# untitled.net
KiCad netlist of a schematic drawn in EAGLE
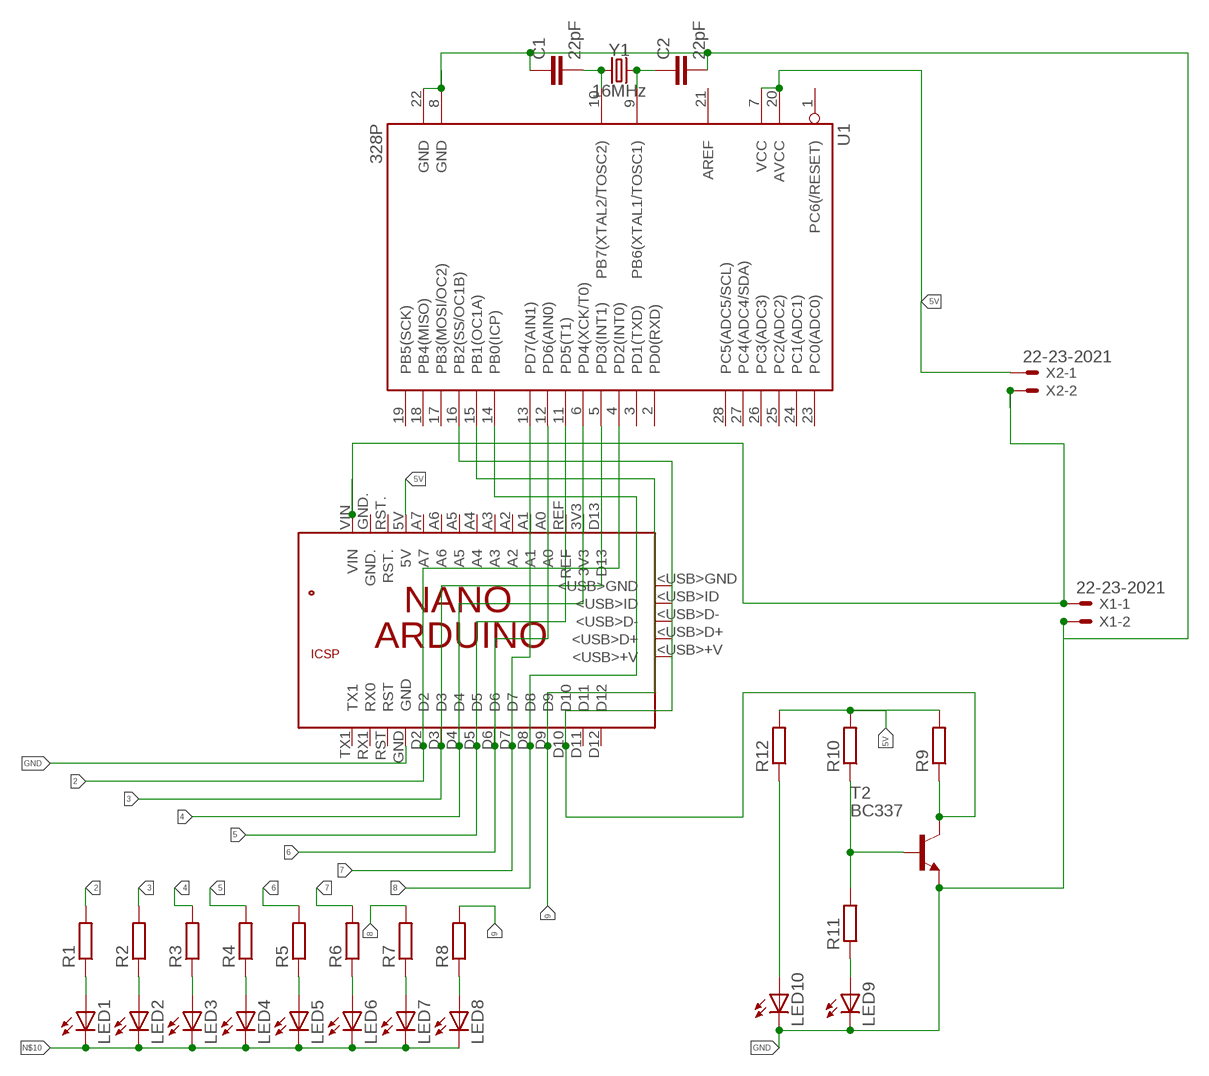
[diagram p0: schematic, sheet 1]

(export (version "E")
  (design (tool "Eeschema 10.0.6"))
  (components
    (comp (ref "C1")
      (value "22pF")
      (footprint "eagle-import:CAP-PTH-2.54")
      (libsource (lib "eagle-import") (part "22PF-PTH-2.54MM-200V-5%"))
    )
    (comp (ref "C2")
      (value "22pF")
      (footprint "eagle-import:CAP-PTH-2.54")
      (libsource (lib "eagle-import") (part "22PF-PTH-2.54MM-200V-5%"))
    )
    (comp (ref "LED1")
      (value "LED5MM")
      (footprint "eagle-import:LED5MM")
      (libsource (lib "eagle-import") (part "LED5MM"))
    )
    (comp (ref "LED2")
      (value "LED5MM")
      (footprint "eagle-import:LED5MM")
      (libsource (lib "eagle-import") (part "LED5MM"))
    )
    (comp (ref "LED3")
      (value "LED5MM")
      (footprint "eagle-import:LED5MM")
      (libsource (lib "eagle-import") (part "LED5MM"))
    )
    (comp (ref "LED4")
      (value "LED5MM")
      (footprint "eagle-import:LED5MM")
      (libsource (lib "eagle-import") (part "LED5MM"))
    )
    (comp (ref "LED5")
      (value "LED5MM")
      (footprint "eagle-import:LED5MM")
      (libsource (lib "eagle-import") (part "LED5MM"))
    )
    (comp (ref "LED6")
      (value "LED5MM")
      (footprint "eagle-import:LED5MM")
      (libsource (lib "eagle-import") (part "LED5MM"))
    )
    (comp (ref "LED7")
      (value "LED5MM")
      (footprint "eagle-import:LED5MM")
      (libsource (lib "eagle-import") (part "LED5MM"))
    )
    (comp (ref "LED8")
      (value "LED5MM")
      (footprint "eagle-import:LED5MM")
      (libsource (lib "eagle-import") (part "LED5MM"))
    )
    (comp (ref "LED9")
      (value "LED5MM")
      (footprint "eagle-import:LED5MM")
      (libsource (lib "eagle-import") (part "LED5MM"))
    )
    (comp (ref "LED10")
      (value "LED5MM")
      (footprint "eagle-import:LED5MM")
      (libsource (lib "eagle-import") (part "LED5MM"))
    )
    (comp (ref "PCB1")
      (value "ARDUINO_NANO")
      (footprint "eagle-import:ARDUINO_NANO")
      (libsource (lib "eagle-import") (part "ARDUINO_NANO"))
    )
    (comp (ref "R1")
      (value "R-EU_0207/10")
      (footprint "eagle-import:0207_10")
      (libsource (lib "eagle-import") (part "R-EU_0207/10"))
    )
    (comp (ref "R2")
      (value "R-EU_0207/10")
      (footprint "eagle-import:0207_10")
      (libsource (lib "eagle-import") (part "R-EU_0207/10"))
    )
    (comp (ref "R3")
      (value "R-EU_0207/10")
      (footprint "eagle-import:0207_10")
      (libsource (lib "eagle-import") (part "R-EU_0207/10"))
    )
    (comp (ref "R4")
      (value "R-EU_0207/10")
      (footprint "eagle-import:0207_10")
      (libsource (lib "eagle-import") (part "R-EU_0207/10"))
    )
    (comp (ref "R5")
      (value "R-EU_0207/10")
      (footprint "eagle-import:0207_10")
      (libsource (lib "eagle-import") (part "R-EU_0207/10"))
    )
    (comp (ref "R6")
      (value "R-EU_0207/10")
      (footprint "eagle-import:0207_10")
      (libsource (lib "eagle-import") (part "R-EU_0207/10"))
    )
    (comp (ref "R7")
      (value "R-EU_0207/10")
      (footprint "eagle-import:0207_10")
      (libsource (lib "eagle-import") (part "R-EU_0207/10"))
    )
    (comp (ref "R8")
      (value "R-EU_0207/10")
      (footprint "eagle-import:0207_10")
      (libsource (lib "eagle-import") (part "R-EU_0207/10"))
    )
    (comp (ref "R9")
      (value "R-EU_0207/10")
      (footprint "eagle-import:0207_10")
      (libsource (lib "eagle-import") (part "R-EU_0207/10"))
    )
    (comp (ref "R10")
      (value "R-EU_0207/10")
      (footprint "eagle-import:0207_10")
      (libsource (lib "eagle-import") (part "R-EU_0207/10"))
    )
    (comp (ref "R11")
      (value "R-EU_0207/10")
      (footprint "eagle-import:0207_10")
      (libsource (lib "eagle-import") (part "R-EU_0207/10"))
    )
    (comp (ref "R12")
      (value "R-EU_0207/10")
      (footprint "eagle-import:0207_10")
      (libsource (lib "eagle-import") (part "R-EU_0207/10"))
    )
    (comp (ref "T2")
      (value "BC337")
      (footprint "eagle-import:TO92")
      (libsource (lib "eagle-import") (part "BC337"))
    )
    (comp (ref "U1")
      (value "328P")
      (footprint "eagle-import:DIP28")
      (libsource (lib "eagle-import") (part "ATMEGA328P_PDIP"))
    )
    (comp (ref "X1")
      (value "22-23-2021")
      (footprint "eagle-import:22-23-2021")
      (fields (field (name "MF") "MOLEX"))
      (libsource (lib "eagle-import") (part "22-23-2021"))
    )
    (comp (ref "X2")
      (value "22-23-2021")
      (footprint "eagle-import:22-23-2021")
      (fields (field (name "MF") "MOLEX"))
      (libsource (lib "eagle-import") (part "con-molex_165_22-23-2021"))
    )
    (comp (ref "Y1")
      (value "16MHz")
      (footprint "eagle-import:HC49US")
      (libsource (lib "eagle-import") (part "CRYSTAL-16MHZPTH-HC49US"))
    )
  )
  (nets
    (net (code "1") (name "2") (class "Default")
      (node (ref "PCB1") (pin "D2") (pinfunction "D2_D2") (pintype "bidirectional"))
      (node (ref "R1") (pin "2") (pinfunction "2_2") (pintype "passive"))
      (node (ref "U1") (pin "4") (pinfunction "PD2(INT0)_4") (pintype "bidirectional"))
    )
    (net (code "2") (name "3") (class "Default")
      (node (ref "PCB1") (pin "D3") (pinfunction "D3_D3") (pintype "bidirectional"))
      (node (ref "R2") (pin "2") (pinfunction "2_2") (pintype "passive"))
      (node (ref "U1") (pin "5") (pinfunction "PD3(INT1)_5") (pintype "bidirectional"))
    )
    (net (code "3") (name "4") (class "Default")
      (node (ref "PCB1") (pin "D4") (pinfunction "D4_D4") (pintype "bidirectional"))
      (node (ref "R3") (pin "2") (pinfunction "2_2") (pintype "passive"))
      (node (ref "U1") (pin "6") (pinfunction "PD4(XCK/T0)_6") (pintype "bidirectional"))
    )
    (net (code "4") (name "5") (class "Default")
      (node (ref "PCB1") (pin "D5") (pinfunction "D5_D5") (pintype "bidirectional"))
      (node (ref "R4") (pin "2") (pinfunction "2_2") (pintype "passive"))
      (node (ref "U1") (pin "11") (pinfunction "PD5(T1)_11") (pintype "bidirectional"))
    )
    (net (code "5") (name "5V") (class "Default")
      (node (ref "PCB1") (pin "5V") (pinfunction "5V_5V") (pintype "bidirectional"))
      (node (ref "R10") (pin "2") (pinfunction "2_2") (pintype "passive"))
      (node (ref "R12") (pin "2") (pinfunction "2_2") (pintype "passive"))
      (node (ref "R9") (pin "2") (pinfunction "2_2") (pintype "passive"))
      (node (ref "U1") (pin "20") (pinfunction "AVCC_20") (pintype "bidirectional"))
      (node (ref "U1") (pin "7") (pinfunction "VCC_7") (pintype "bidirectional"))
      (node (ref "X2") (pin "1") (pinfunction "S_1") (pintype "passive"))
    )
    (net (code "6") (name "6") (class "Default")
      (node (ref "PCB1") (pin "D6") (pinfunction "D6_D6") (pintype "bidirectional"))
      (node (ref "R5") (pin "2") (pinfunction "2_2") (pintype "passive"))
      (node (ref "U1") (pin "12") (pinfunction "PD6(AIN0)_12") (pintype "bidirectional"))
    )
    (net (code "7") (name "7") (class "Default")
      (node (ref "PCB1") (pin "D7") (pinfunction "D7_D7") (pintype "bidirectional"))
      (node (ref "R6") (pin "2") (pinfunction "2_2") (pintype "passive"))
      (node (ref "U1") (pin "13") (pinfunction "PD7(AIN1)_13") (pintype "bidirectional"))
    )
    (net (code "8") (name "8") (class "Default")
      (node (ref "PCB1") (pin "D8") (pinfunction "D8_D8") (pintype "bidirectional"))
      (node (ref "R7") (pin "2") (pinfunction "2_2") (pintype "passive"))
      (node (ref "U1") (pin "14") (pinfunction "PB0(ICP)_14") (pintype "bidirectional"))
    )
    (net (code "9") (name "9") (class "Default")
      (node (ref "PCB1") (pin "D9") (pinfunction "D9_D9") (pintype "bidirectional"))
      (node (ref "R8") (pin "2") (pinfunction "2_2") (pintype "passive"))
      (node (ref "U1") (pin "15") (pinfunction "PB1(OC1A)_15") (pintype "bidirectional"))
    )
    (net (code "10") (name "GND") (class "Default")
      (node (ref "C1") (pin "1") (pinfunction "1_1") (pintype "passive"))
      (node (ref "C2") (pin "2") (pinfunction "2_2") (pintype "passive"))
      (node (ref "LED10") (pin "K") (pinfunction "C_K") (pintype "passive"))
      (node (ref "LED9") (pin "K") (pinfunction "C_K") (pintype "passive"))
      (node (ref "PCB1") (pin "GND") (pinfunction "GND_GND") (pintype "bidirectional"))
      (node (ref "T2") (pin "1") (pinfunction "E_1") (pintype "passive"))
      (node (ref "U1") (pin "22") (pinfunction "GND_22") (pintype "bidirectional"))
      (node (ref "U1") (pin "8") (pinfunction "GND_8") (pintype "bidirectional"))
      (node (ref "X1") (pin "2") (pinfunction "S_2") (pintype "passive"))
    )
    (net (code "11") (name "N$10") (class "Default")
      (node (ref "LED1") (pin "K") (pinfunction "C_K") (pintype "passive"))
      (node (ref "LED2") (pin "K") (pinfunction "C_K") (pintype "passive"))
      (node (ref "LED3") (pin "K") (pinfunction "C_K") (pintype "passive"))
      (node (ref "LED4") (pin "K") (pinfunction "C_K") (pintype "passive"))
      (node (ref "LED5") (pin "K") (pinfunction "C_K") (pintype "passive"))
      (node (ref "LED6") (pin "K") (pinfunction "C_K") (pintype "passive"))
      (node (ref "LED7") (pin "K") (pinfunction "C_K") (pintype "passive"))
      (node (ref "LED8") (pin "K") (pinfunction "C_K") (pintype "passive"))
    )
    (net (code "12") (name "Net-(LED1-PadA)") (class "Default")
      (node (ref "LED1") (pin "A") (pinfunction "A_A") (pintype "passive"))
      (node (ref "R1") (pin "1") (pinfunction "1_1") (pintype "passive"))
    )
    (net (code "13") (name "Net-(LED2-PadA)") (class "Default")
      (node (ref "LED2") (pin "A") (pinfunction "A_A") (pintype "passive"))
      (node (ref "R2") (pin "1") (pinfunction "1_1") (pintype "passive"))
    )
    (net (code "14") (name "Net-(LED3-PadA)") (class "Default")
      (node (ref "LED3") (pin "A") (pinfunction "A_A") (pintype "passive"))
      (node (ref "R3") (pin "1") (pinfunction "1_1") (pintype "passive"))
    )
    (net (code "15") (name "Net-(LED4-PadA)") (class "Default")
      (node (ref "LED4") (pin "A") (pinfunction "A_A") (pintype "passive"))
      (node (ref "R4") (pin "1") (pinfunction "1_1") (pintype "passive"))
    )
    (net (code "16") (name "Net-(LED5-PadA)") (class "Default")
      (node (ref "LED5") (pin "A") (pinfunction "A_A") (pintype "passive"))
      (node (ref "R5") (pin "1") (pinfunction "1_1") (pintype "passive"))
    )
    (net (code "17") (name "Net-(LED6-PadA)") (class "Default")
      (node (ref "LED6") (pin "A") (pinfunction "A_A") (pintype "passive"))
      (node (ref "R6") (pin "1") (pinfunction "1_1") (pintype "passive"))
    )
    (net (code "18") (name "Net-(LED7-PadA)") (class "Default")
      (node (ref "LED7") (pin "A") (pinfunction "A_A") (pintype "passive"))
      (node (ref "R7") (pin "1") (pinfunction "1_1") (pintype "passive"))
    )
    (net (code "19") (name "Net-(LED8-PadA)") (class "Default")
      (node (ref "LED8") (pin "A") (pinfunction "A_A") (pintype "passive"))
      (node (ref "R8") (pin "1") (pinfunction "1_1") (pintype "passive"))
    )
    (net (code "20") (name "Net-(LED9-PadA)") (class "Default")
      (node (ref "LED9") (pin "A") (pinfunction "A_A") (pintype "passive"))
      (node (ref "R11") (pin "1") (pinfunction "1_1") (pintype "passive"))
    )
    (net (code "21") (name "Net-(LED10-PadA)") (class "Default")
      (node (ref "LED10") (pin "A") (pinfunction "A_A") (pintype "passive"))
      (node (ref "R12") (pin "1") (pinfunction "1_1") (pintype "passive"))
    )
    (net (code "22") (name "Net-(T2-B)") (class "Default")
      (node (ref "R10") (pin "1") (pinfunction "1_1") (pintype "passive"))
      (node (ref "R11") (pin "2") (pinfunction "2_2") (pintype "passive"))
      (node (ref "T2") (pin "2") (pinfunction "B_2") (pintype "passive"))
    )
    (net (code "23") (name "Net-(T2-C)") (class "Default")
      (node (ref "PCB1") (pin "D10") (pinfunction "D10_D10") (pintype "bidirectional"))
      (node (ref "R9") (pin "1") (pinfunction "1_1") (pintype "passive"))
      (node (ref "T2") (pin "3") (pinfunction "C_3") (pintype "passive"))
      (node (ref "U1") (pin "16") (pinfunction "PB2(SS/OC1B)_16") (pintype "bidirectional"))
    )
    (net (code "24") (name "Net-(U1-PB6(XTAL1{slash}TOSC1))") (class "Default")
      (node (ref "C2") (pin "1") (pinfunction "1_1") (pintype "passive"))
      (node (ref "U1") (pin "9") (pinfunction "PB6(XTAL1/TOSC1)_9") (pintype "bidirectional"))
      (node (ref "Y1") (pin "2") (pinfunction "2_2") (pintype "passive"))
    )
    (net (code "25") (name "Net-(U1-PB7(XTAL2{slash}TOSC2))") (class "Default")
      (node (ref "C1") (pin "2") (pinfunction "2_2") (pintype "passive"))
      (node (ref "U1") (pin "10") (pinfunction "PB7(XTAL2/TOSC2)_10") (pintype "bidirectional"))
      (node (ref "Y1") (pin "1") (pinfunction "1_1") (pintype "passive"))
    )
    (net (code "26") (name "Net-(X1A-S)") (class "Default")
      (node (ref "PCB1") (pin "VIN") (pinfunction "VIN_VIN") (pintype "bidirectional"))
      (node (ref "X1") (pin "1") (pinfunction "S_1") (pintype "passive"))
      (node (ref "X2") (pin "2") (pinfunction "S_2") (pintype "passive"))
    )
    (net (code "27") (name "unconnected-(PCB1-Pad3V3)") (class "Default")
      (node (ref "PCB1") (pin "3V3") (pinfunction "3V3_3V3") (pintype "bidirectional"))
    )
    (net (code "28") (name "unconnected-(PCB1-Pad5V.)") (class "Default")
      (node (ref "PCB1") (pin "5V.") (pinfunction "5V._5V.") (pintype "bidirectional"))
    )
    (net (code "29") (name "unconnected-(PCB1-Pad<USB>+V)") (class "Default")
      (node (ref "PCB1") (pin "<USB>+V") (pinfunction "<USB>+V_<USB>+V") (pintype "bidirectional"))
    )
    (net (code "30") (name "unconnected-(PCB1-Pad<USB>D+)") (class "Default")
      (node (ref "PCB1") (pin "<USB>D+") (pinfunction "<USB>D+_<USB>D+") (pintype "bidirectional"))
    )
    (net (code "31") (name "unconnected-(PCB1-Pad<USB>D-)") (class "Default")
      (node (ref "PCB1") (pin "<USB>D-") (pinfunction "<USB>D-_<USB>D-") (pintype "bidirectional"))
    )
    (net (code "32") (name "unconnected-(PCB1-Pad<USB>GND)") (class "Default")
      (node (ref "PCB1") (pin "<USB>GND") (pinfunction "<USB>GND_<USB>GND") (pintype "bidirectional"))
    )
    (net (code "33") (name "unconnected-(PCB1-Pad<USB>ID)") (class "Default")
      (node (ref "PCB1") (pin "<USB>ID") (pinfunction "<USB>ID_<USB>ID") (pintype "bidirectional"))
    )
    (net (code "34") (name "unconnected-(PCB1-PadA0)") (class "Default")
      (node (ref "PCB1") (pin "A0") (pinfunction "A0_A0") (pintype "bidirectional"))
    )
    (net (code "35") (name "unconnected-(PCB1-PadA1)") (class "Default")
      (node (ref "PCB1") (pin "A1") (pinfunction "A1_A1") (pintype "bidirectional"))
    )
    (net (code "36") (name "unconnected-(PCB1-PadA2)") (class "Default")
      (node (ref "PCB1") (pin "A2") (pinfunction "A2_A2") (pintype "bidirectional"))
    )
    (net (code "37") (name "unconnected-(PCB1-PadA3)") (class "Default")
      (node (ref "PCB1") (pin "A3") (pinfunction "A3_A3") (pintype "bidirectional"))
    )
    (net (code "38") (name "unconnected-(PCB1-PadA4)") (class "Default")
      (node (ref "PCB1") (pin "A4") (pinfunction "A4_A4") (pintype "bidirectional"))
    )
    (net (code "39") (name "unconnected-(PCB1-PadA5)") (class "Default")
      (node (ref "PCB1") (pin "A5") (pinfunction "A5_A5") (pintype "bidirectional"))
    )
    (net (code "40") (name "unconnected-(PCB1-PadA6)") (class "Default")
      (node (ref "PCB1") (pin "A6") (pinfunction "A6_A6") (pintype "bidirectional"))
    )
    (net (code "41") (name "unconnected-(PCB1-PadA7)") (class "Default")
      (node (ref "PCB1") (pin "A7") (pinfunction "A7_A7") (pintype "bidirectional"))
    )
    (net (code "42") (name "unconnected-(PCB1-PadD11)") (class "Default")
      (node (ref "PCB1") (pin "D11") (pinfunction "D11_D11") (pintype "bidirectional"))
    )
    (net (code "43") (name "unconnected-(PCB1-PadD12)") (class "Default")
      (node (ref "PCB1") (pin "D12") (pinfunction "D12_D12") (pintype "bidirectional"))
    )
    (net (code "44") (name "unconnected-(PCB1-PadD13)") (class "Default")
      (node (ref "PCB1") (pin "D13") (pinfunction "D13_D13") (pintype "bidirectional"))
    )
    (net (code "45") (name "unconnected-(PCB1-PadGND.)") (class "Default")
      (node (ref "PCB1") (pin "GND.") (pinfunction "GND._GND.") (pintype "bidirectional"))
    )
    (net (code "46") (name "unconnected-(PCB1-PadGND_)") (class "Default")
      (node (ref "PCB1") (pin "GND_") (pinfunction "GND__GND_") (pintype "bidirectional"))
    )
    (net (code "47") (name "unconnected-(PCB1-PadMISO)") (class "Default")
      (node (ref "PCB1") (pin "MISO") (pinfunction "MISO_MISO") (pintype "bidirectional"))
    )
    (net (code "48") (name "unconnected-(PCB1-PadMOSI)") (class "Default")
      (node (ref "PCB1") (pin "MOSI") (pinfunction "MOSI_MOSI") (pintype "bidirectional"))
    )
    (net (code "49") (name "unconnected-(PCB1-PadREF)") (class "Default")
      (node (ref "PCB1") (pin "REF") (pinfunction "REF_REF") (pintype "bidirectional"))
    )
    (net (code "50") (name "unconnected-(PCB1-PadRESET..)") (class "Default")
      (node (ref "PCB1") (pin "RESET..") (pinfunction "RESET.._RESET..") (pintype "bidirectional"))
    )
    (net (code "51") (name "unconnected-(PCB1-PadRST)") (class "Default")
      (node (ref "PCB1") (pin "RST") (pinfunction "RST_RST") (pintype "bidirectional"))
    )
    (net (code "52") (name "unconnected-(PCB1-PadRST.)") (class "Default")
      (node (ref "PCB1") (pin "RST.") (pinfunction "RST._RST.") (pintype "bidirectional"))
    )
    (net (code "53") (name "unconnected-(PCB1-PadSCK)") (class "Default")
      (node (ref "PCB1") (pin "SCK") (pinfunction "SCK_SCK") (pintype "bidirectional"))
    )
    (net (code "54") (name "unconnected-(PCB1-PadTX1)") (class "Default")
      (node (ref "PCB1") (pin "TX1") (pinfunction "TX1_TX1") (pintype "bidirectional"))
    )
    (net (code "55") (name "unconnected-(PCB1-RX0-PadRX1)") (class "Default")
      (node (ref "PCB1") (pin "RX1") (pinfunction "RX0_RX1") (pintype "bidirectional"))
    )
    (net (code "56") (name "unconnected-(U1-AREF-Pad21)") (class "Default")
      (node (ref "U1") (pin "21") (pinfunction "AREF_21") (pintype "bidirectional"))
    )
    (net (code "57") (name "unconnected-(U1-PB3(MOSI{slash}OC2)-Pad17)") (class "Default")
      (node (ref "U1") (pin "17") (pinfunction "PB3(MOSI/OC2)_17") (pintype "bidirectional"))
    )
    (net (code "58") (name "unconnected-(U1-PB4(MISO)-Pad18)") (class "Default")
      (node (ref "U1") (pin "18") (pinfunction "PB4(MISO)_18") (pintype "bidirectional"))
    )
    (net (code "59") (name "unconnected-(U1-PB5(SCK)-Pad19)") (class "Default")
      (node (ref "U1") (pin "19") (pinfunction "PB5(SCK)_19") (pintype "bidirectional"))
    )
    (net (code "60") (name "unconnected-(U1-PC0(ADC0)-Pad23)") (class "Default")
      (node (ref "U1") (pin "23") (pinfunction "PC0(ADC0)_23") (pintype "bidirectional"))
    )
    (net (code "61") (name "unconnected-(U1-PC1(ADC1)-Pad24)") (class "Default")
      (node (ref "U1") (pin "24") (pinfunction "PC1(ADC1)_24") (pintype "bidirectional"))
    )
    (net (code "62") (name "unconnected-(U1-PC2(ADC2)-Pad25)") (class "Default")
      (node (ref "U1") (pin "25") (pinfunction "PC2(ADC2)_25") (pintype "bidirectional"))
    )
    (net (code "63") (name "unconnected-(U1-PC3(ADC3)-Pad26)") (class "Default")
      (node (ref "U1") (pin "26") (pinfunction "PC3(ADC3)_26") (pintype "bidirectional"))
    )
    (net (code "64") (name "unconnected-(U1-PC4(ADC4{slash}SDA)-Pad27)") (class "Default")
      (node (ref "U1") (pin "27") (pinfunction "PC4(ADC4/SDA)_27") (pintype "bidirectional"))
    )
    (net (code "65") (name "unconnected-(U1-PC5(ADC5{slash}SCL)-Pad28)") (class "Default")
      (node (ref "U1") (pin "28") (pinfunction "PC5(ADC5/SCL)_28") (pintype "bidirectional"))
    )
    (net (code "66") (name "unconnected-(U1-PC6({slash}RESET)-Pad1)") (class "Default")
      (node (ref "U1") (pin "1") (pinfunction "PC6(/RESET)_1") (pintype "bidirectional"))
    )
    (net (code "67") (name "unconnected-(U1-PD0(RXD)-Pad2)") (class "Default")
      (node (ref "U1") (pin "2") (pinfunction "PD0(RXD)_2") (pintype "bidirectional"))
    )
    (net (code "68") (name "unconnected-(U1-PD1(TXD)-Pad3)") (class "Default")
      (node (ref "U1") (pin "3") (pinfunction "PD1(TXD)_3") (pintype "bidirectional"))
    )
  )
)
